# PowerMCU.net
KiCad netlist of a schematic drawn in Altium Designer
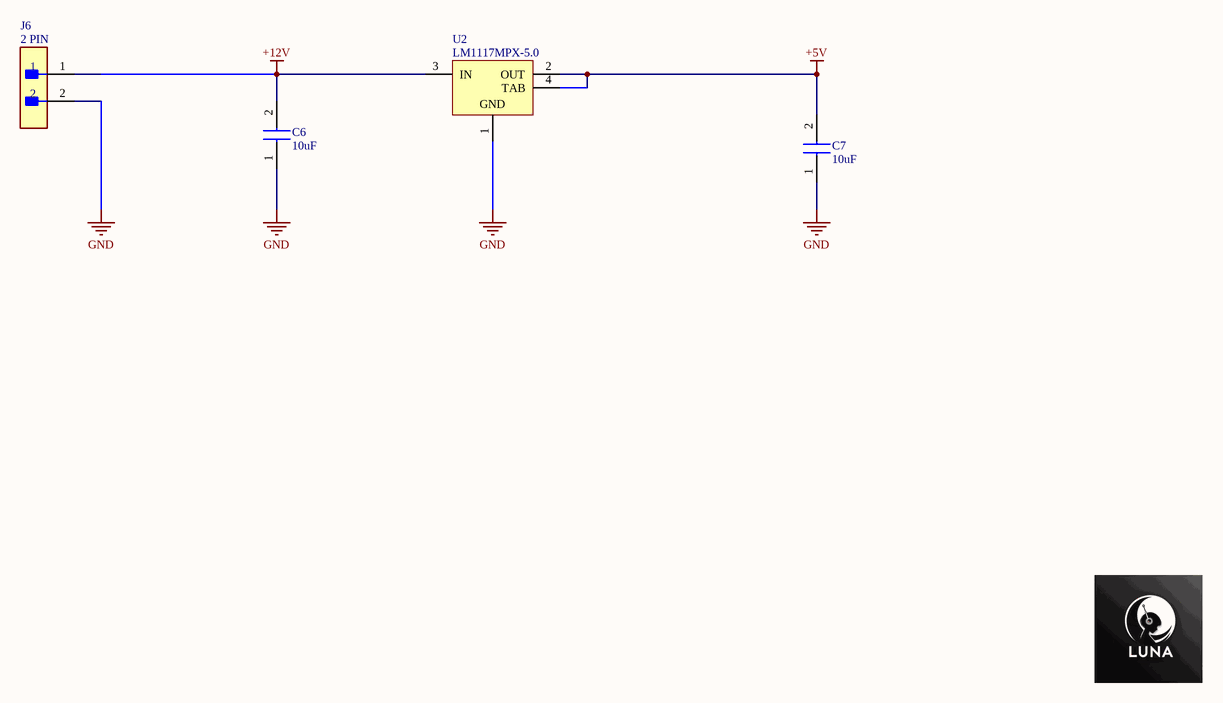
[diagram p0: PowerMCU.SchDoc]

(export (version "E")
  (design (tool "Eeschema 10.0.6"))
  (components
    (comp (ref "C6")
      (value "10uF")
      (footprint "SamacSys:CAPC1608X90N")
      (description "CL10A106KP8NNNC Capacitor")
      (fields
        (field (name "MANUFACTURER_PART_NUMBER") "CL10A106KP8NNNC")
        (field (name "MOUSER PART NUMBER") "187-CL10A106KP8NNNC")
      )
      (libsource (lib "*") (part "CL10A106KP8NNNC"))
    )
    (comp (ref "C7")
      (value "10uF")
      (footprint "SamacSys:CAPC1608X90N")
      (description "CL10A106KP8NNNC Capacitor")
      (fields
        (field (name "MANUFACTURER_PART_NUMBER") "CL10A106KP8NNNC")
        (field (name "MOUSER PART NUMBER") "187-CL10A106KP8NNNC")
      )
      (libsource (lib "*") (part "CL10A106KP8NNNC"))
    )
    (comp (ref "J6")
      (value "2 PIN")
      (footprint "FP-B2B-XH-AM_LF_SN-MFG")
      (description "CONN HEADER VERT 2POS 2.5MM")
      (libsource (lib "Altium Content Vault") (part "3bc925449376181038e59eaffc5286c"))
    )
    (comp (ref "U2")
      (value "LM1117MPX-5.0")
      (footprint "DCY0004A_L")
      (description "800mA Low-Dropout Linear Regulator, 4-pin SOT-223")
      (fields (field (name "MANUFACTURER") "Texas Instruments"))
      (libsource (lib "Altium Content Vault") (part "PM-REG-LM1086-SOT4"))
    )
  )
  (nets
    (net (code "1") (name "+5V") (class "Default")
      (node (ref "C7") (pin "2") (pinfunction "2_2") (pintype "passive"))
      (node (ref "U2") (pin "2") (pinfunction "OUT_2") (pintype "power_in"))
      (node (ref "U2") (pin "4") (pinfunction "TAB_4") (pintype "power_in"))
    )
    (net (code "2") (name "+12V") (class "Default")
      (node (ref "C6") (pin "2") (pinfunction "2_2") (pintype "passive"))
      (node (ref "J6") (pin "1") (pinfunction "1_1") (pintype "passive"))
      (node (ref "U2") (pin "3") (pinfunction "IN_3") (pintype "power_in"))
    )
    (net (code "3") (name "GND") (class "Default")
      (node (ref "C6") (pin "1") (pinfunction "1_1") (pintype "passive"))
      (node (ref "C7") (pin "1") (pinfunction "1_1") (pintype "passive"))
      (node (ref "J6") (pin "2") (pinfunction "2_2") (pintype "passive"))
      (node (ref "U2") (pin "1") (pinfunction "GND_1") (pintype "power_in"))
    )
  )
)
